# rs422-rs485.net
KiCad netlist of a schematic drawn in Altium Designer
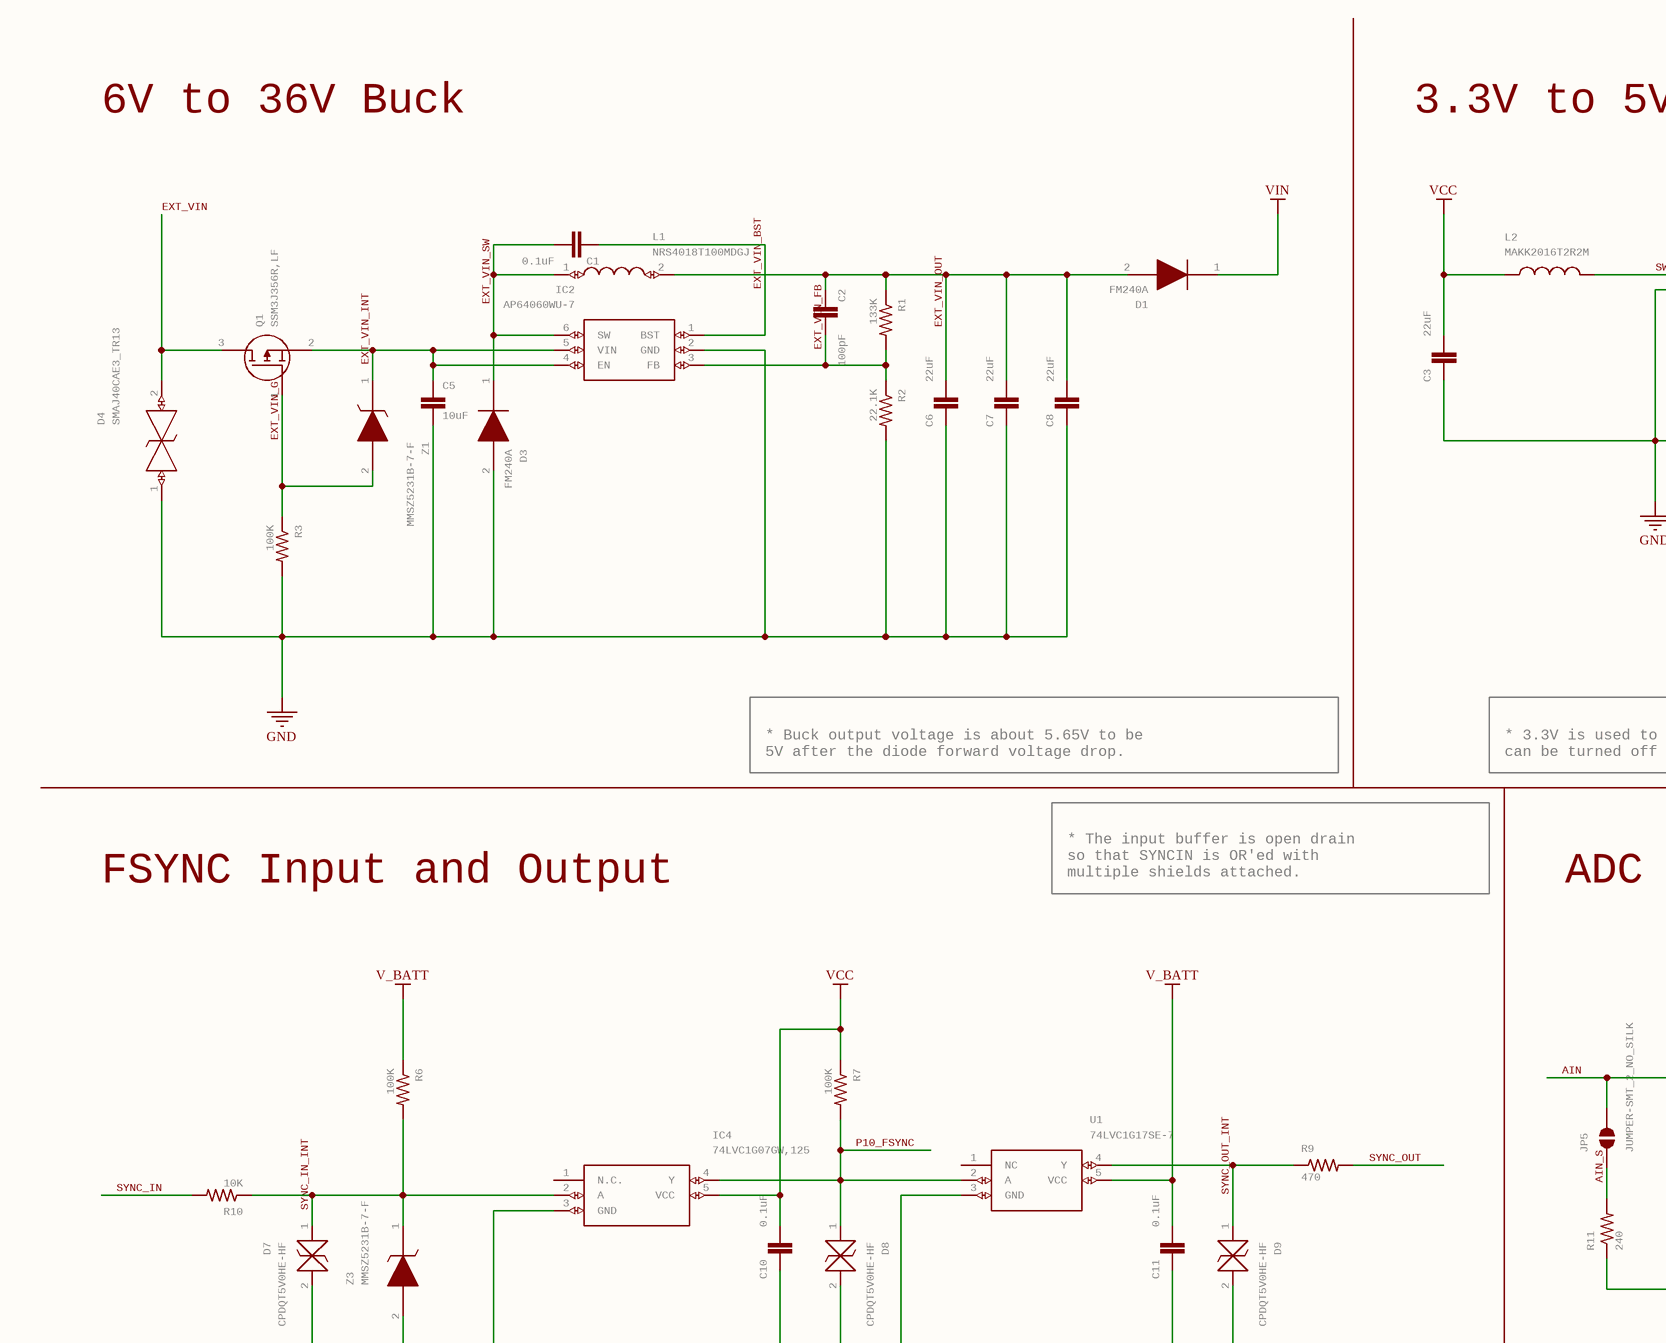
[diagram p0: rs422-rs485.SchDoc, top left]
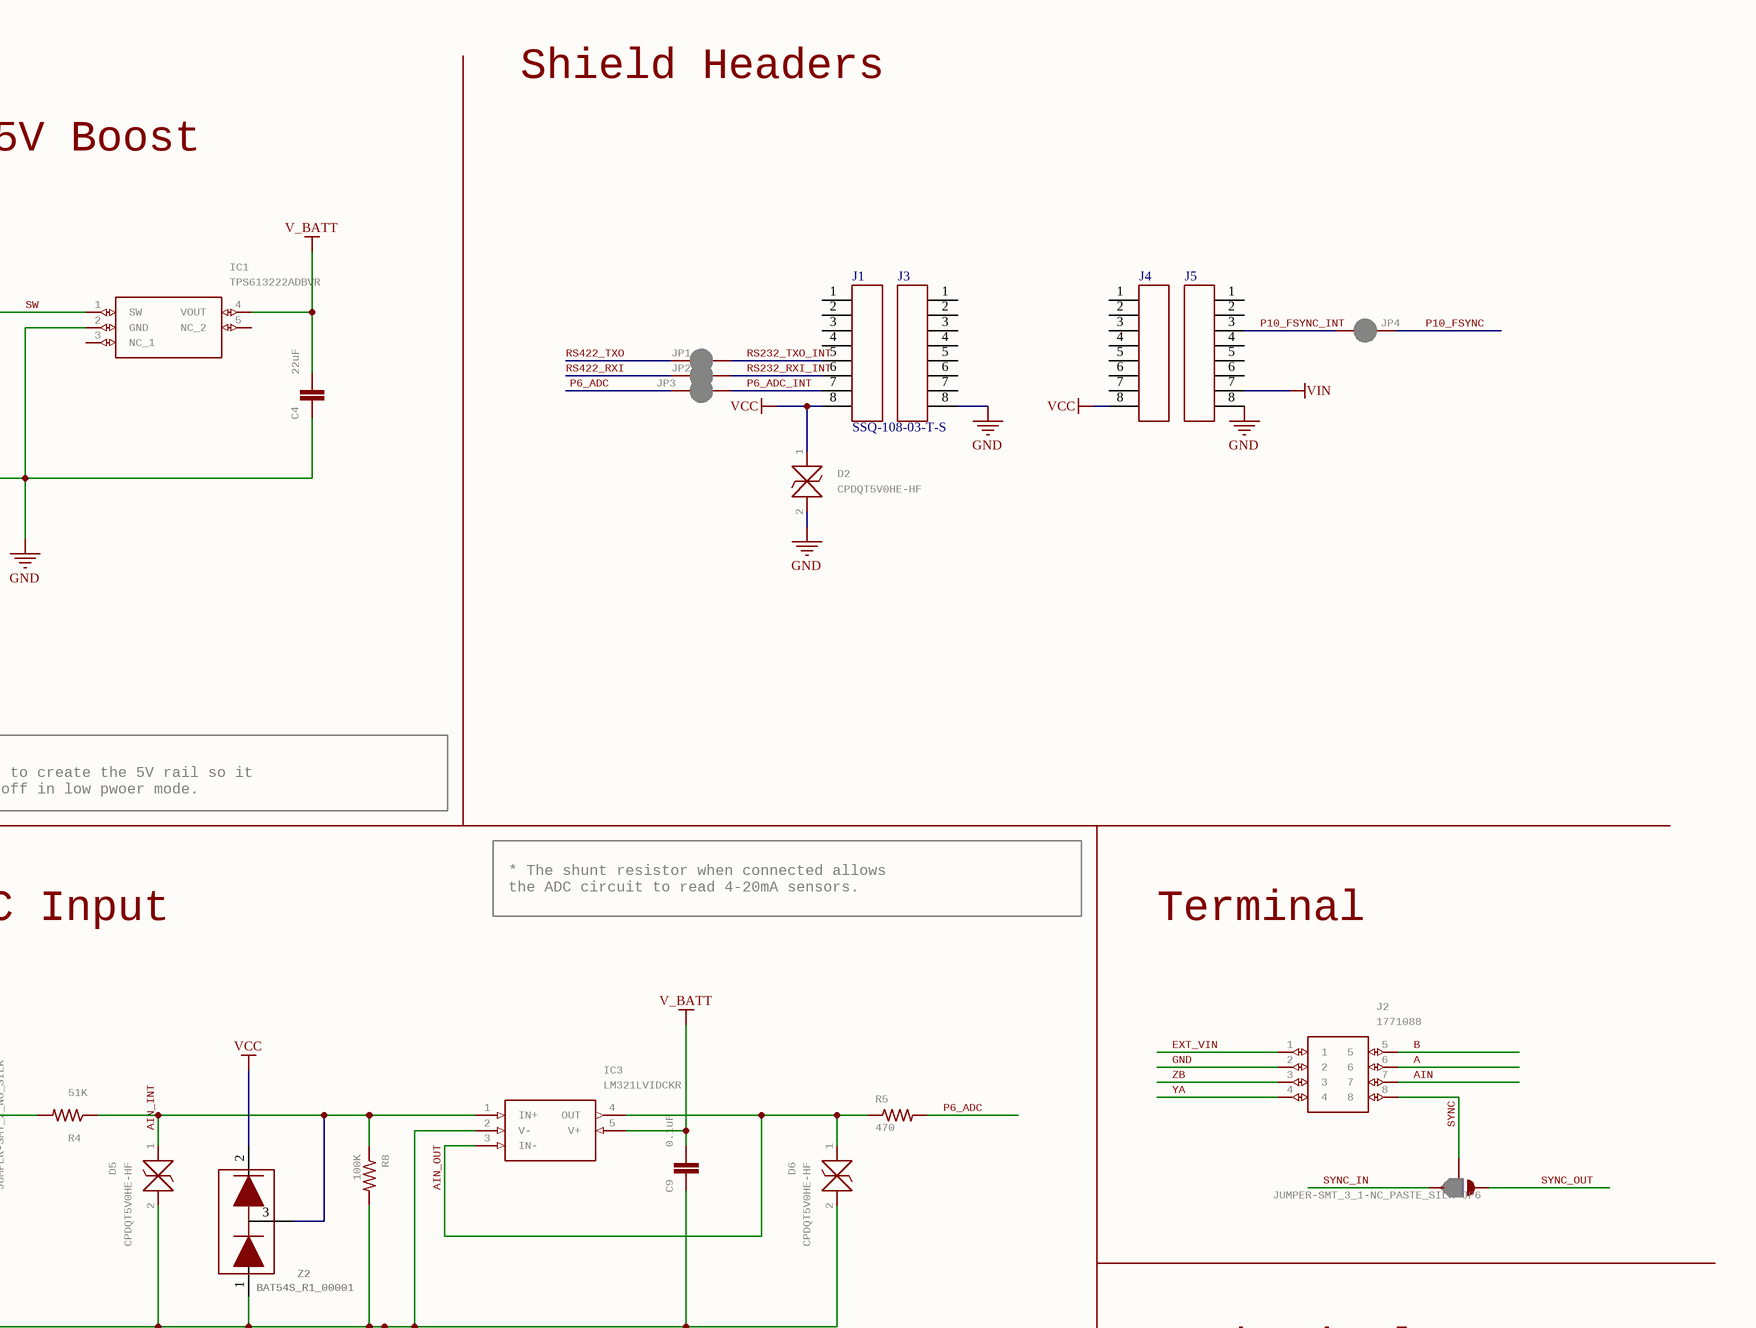
[diagram p1: rs422-rs485.SchDoc, top right]
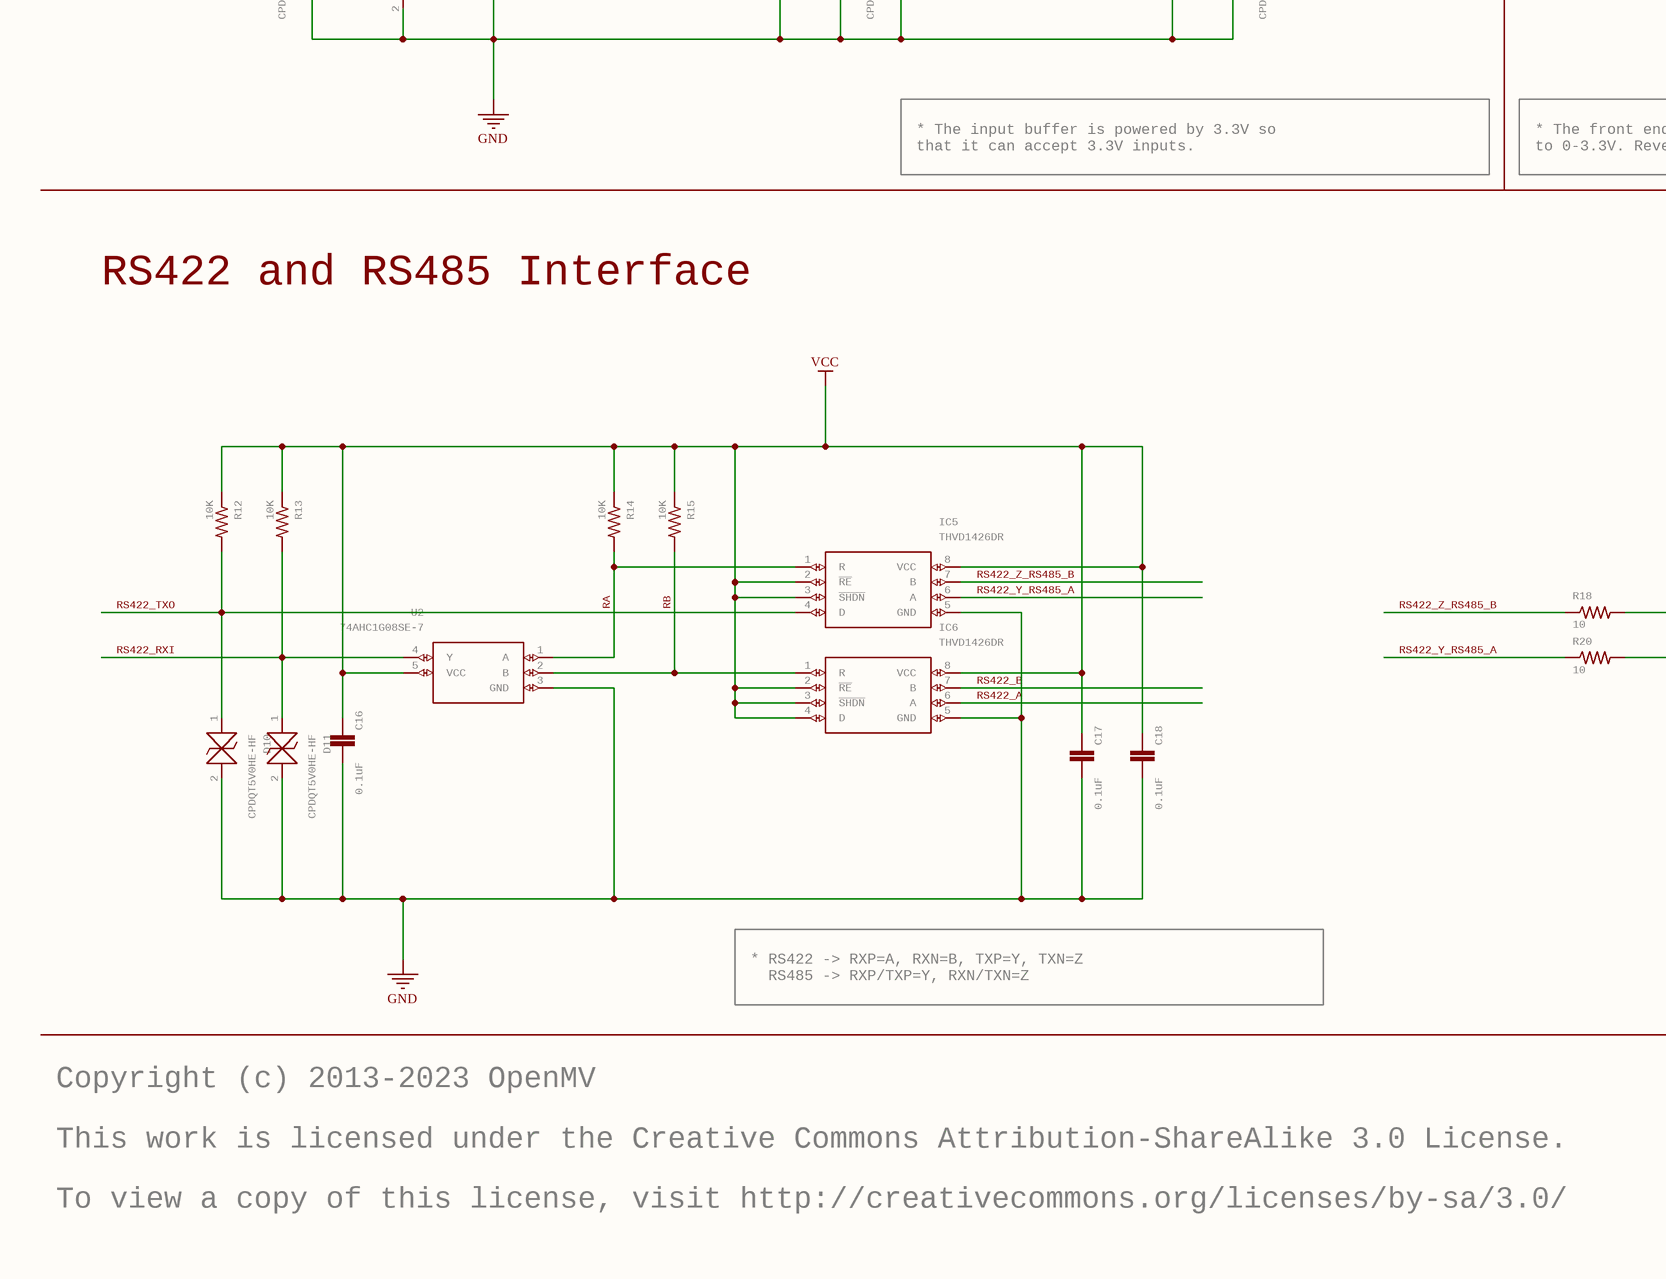
[diagram p2: rs422-rs485.SchDoc, bottom left]
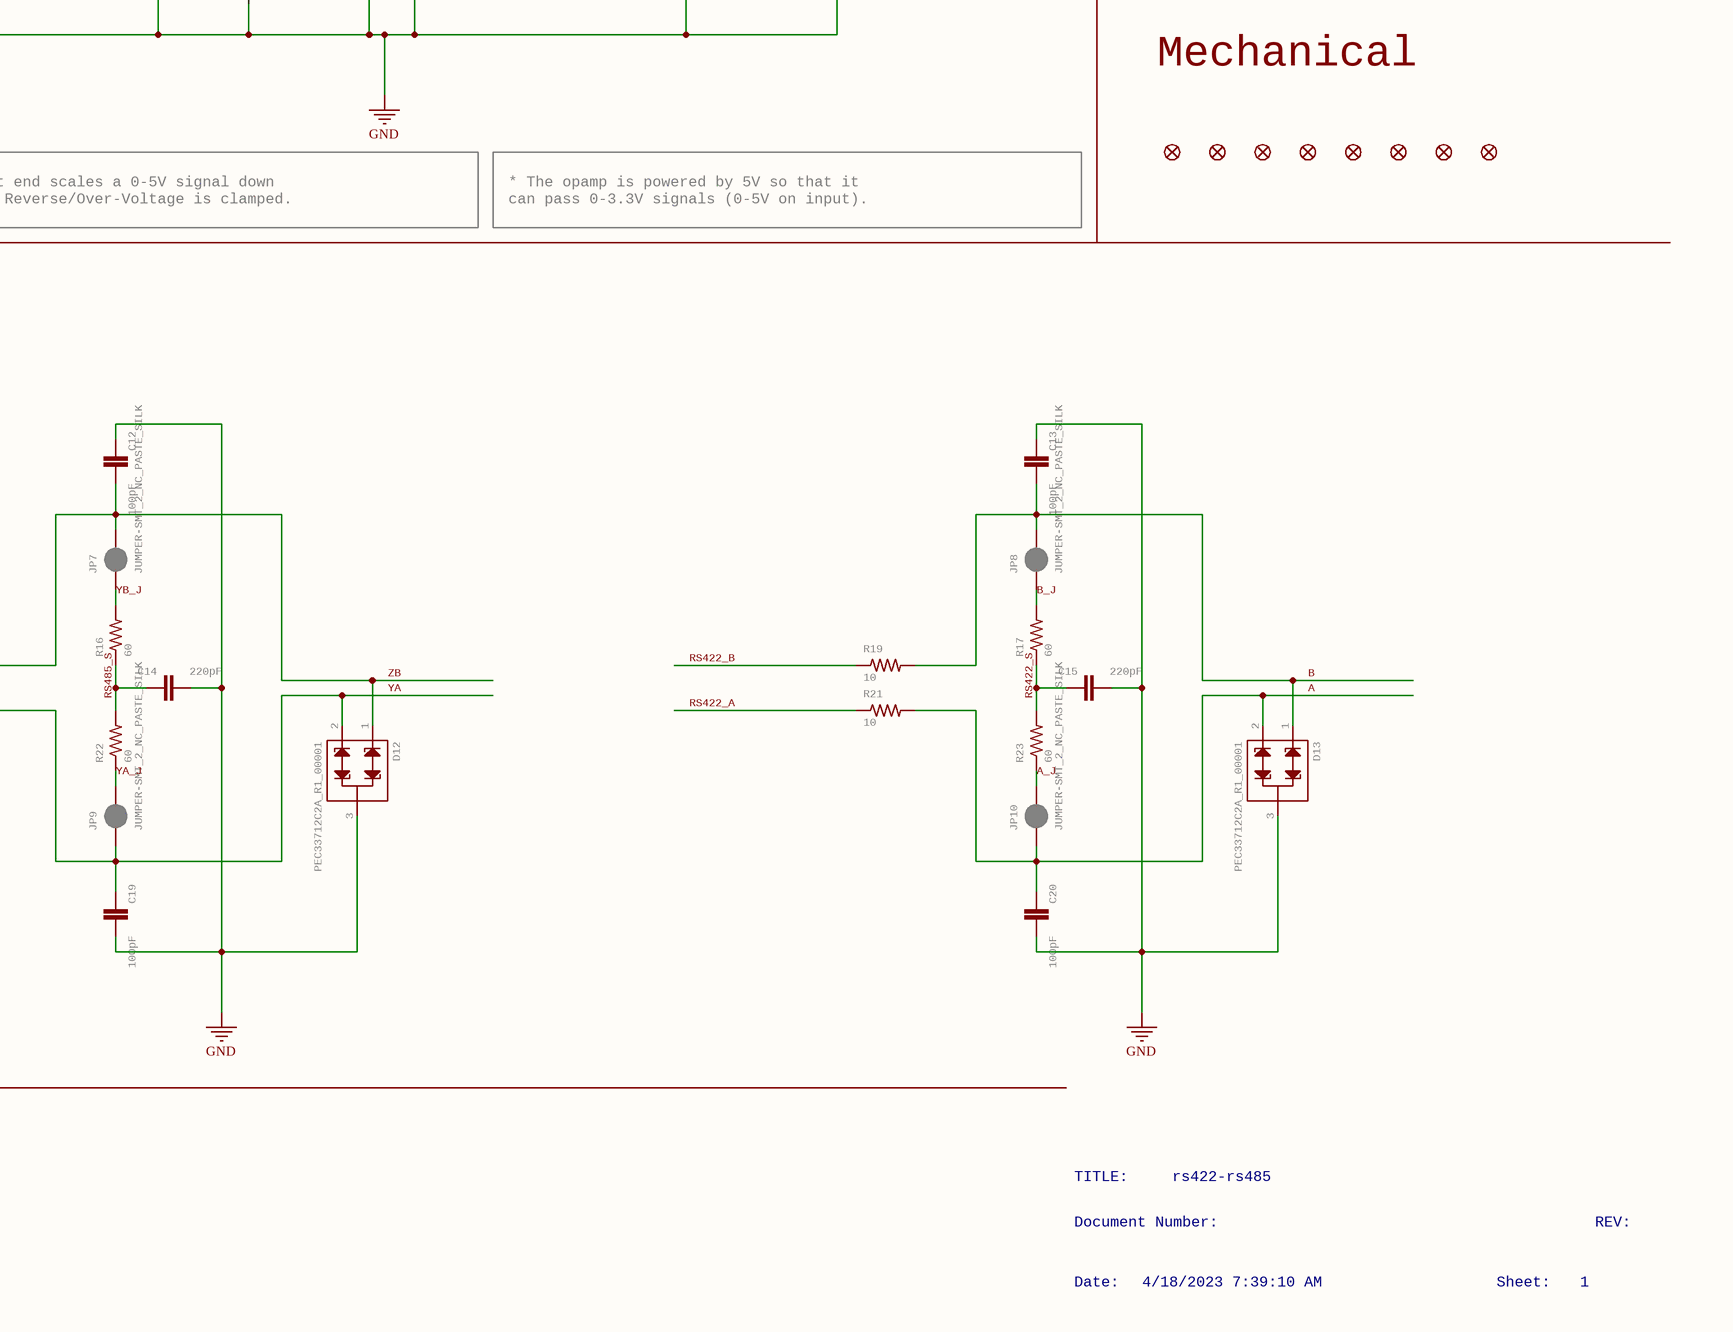
[diagram p3: rs422-rs485.SchDoc, bottom right]

(export (version "E")
  (design (tool "Eeschema 10.0.6"))
  (components
    (comp (ref "C1")
      (value "0.1uF")
      (footprint "0402-CAP")
      (description "CapacitorStandard 0603 ceramic capacitor, and 0.1\" leaded capacitor.")
      (fields (field (name "MPN") "GRM155R71H104KE14D"))
      (libsource (lib "") (part "CAP0402-CAP_3"))
    )
    (comp (ref "C2")
      (value "100pF")
      (footprint "0402-CAP")
      (description "CapacitorStandard 0603 ceramic capacitor, and 0.1\" leaded capacitor.")
      (fields (field (name "MPN") "CC0402JRNPO9BN101"))
      (libsource (lib "rs422-rs485") (part "CAP0402-CAP"))
    )
    (comp (ref "C3")
      (value "22uF")
      (footprint "0805")
      (fields (field (name "MPN") "CL21A226MQQNNNE"))
      (libsource (lib "rs422-rs485") (part "22UF-0805-6.3V-20%"))
    )
    (comp (ref "C4")
      (value "22uF")
      (footprint "0805")
      (fields (field (name "MPN") "CL21A226MQQNNNE"))
      (libsource (lib "rs422-rs485") (part "22UF-0805-6.3V-20%"))
    )
    (comp (ref "C5")
      (value "10uF")
      (footprint "C0805")
      (description "CAPACITOR, European symbol")
      (fields (field (name "MPN") "GRM21BR61H106KE43K"))
      (libsource (lib "rs422-rs485") (part "C-EUC0805"))
    )
    (comp (ref "C6")
      (value "22uF")
      (footprint "0805")
      (fields (field (name "MPN") "CL21A226MQQNNNE"))
      (libsource (lib "rs422-rs485") (part "22UF-0805-6.3V-20%"))
    )
    (comp (ref "C7")
      (value "22uF")
      (footprint "0805")
      (fields (field (name "MPN") "CL21A226MQQNNNE"))
      (libsource (lib "rs422-rs485") (part "22UF-0805-6.3V-20%"))
    )
    (comp (ref "C8")
      (value "22uF")
      (footprint "0805")
      (fields (field (name "MPN") "CL21A226MQQNNNE"))
      (libsource (lib "rs422-rs485") (part "22UF-0805-6.3V-20%"))
    )
    (comp (ref "C9")
      (value "0.1uF")
      (footprint "0402-CAP")
      (description "CapacitorStandard 0603 ceramic capacitor, and 0.1\" leaded capacitor.")
      (fields (field (name "MPN") "GRM155R71H104KE14D"))
      (libsource (lib "") (part "CAP0402-CAP_1"))
    )
    (comp (ref "C10")
      (value "0.1uF")
      (footprint "0402-CAP")
      (description "CapacitorStandard 0603 ceramic capacitor, and 0.1\" leaded capacitor.")
      (fields (field (name "MPN") "GRM155R71H104KE14D"))
      (libsource (lib "") (part "CAP0402-CAP_1"))
    )
    (comp (ref "C11")
      (value "0.1uF")
      (footprint "0402-CAP")
      (description "CapacitorStandard 0603 ceramic capacitor, and 0.1\" leaded capacitor.")
      (fields (field (name "MPN") "GRM155R71H104KE14D"))
      (libsource (lib "") (part "CAP0402-CAP_1"))
    )
    (comp (ref "C12")
      (value "100pF")
      (footprint "0402-CAP")
      (description "CapacitorStandard 0603 ceramic capacitor, and 0.1\" leaded capacitor.")
      (fields (field (name "MPN") "CC0402JRNPO9BN101"))
      (libsource (lib "rs422-rs485") (part "CAP0402-CAP"))
    )
    (comp (ref "C13")
      (value "100pF")
      (footprint "0402-CAP")
      (description "CapacitorStandard 0603 ceramic capacitor, and 0.1\" leaded capacitor.")
      (fields (field (name "MPN") "CC0402JRNPO9BN101"))
      (libsource (lib "rs422-rs485") (part "CAP0402-CAP"))
    )
    (comp (ref "C14")
      (value "220pF")
      (footprint "0402-CAP")
      (description "CapacitorStandard 0603 ceramic capacitor, and 0.1\" leaded capacitor.")
      (fields (field (name "MPN") "0402B221K500CT"))
      (libsource (lib "") (part "CAP0402-CAP_2"))
    )
    (comp (ref "C15")
      (value "220pF")
      (footprint "0402-CAP")
      (description "CapacitorStandard 0603 ceramic capacitor, and 0.1\" leaded capacitor.")
      (fields (field (name "MPN") "0402B221K500CT"))
      (libsource (lib "") (part "CAP0402-CAP_2"))
    )
    (comp (ref "C16")
      (value "0.1uF")
      (footprint "0402-CAP")
      (description "CapacitorStandard 0603 ceramic capacitor, and 0.1\" leaded capacitor.")
      (fields (field (name "MPN") "GRM155R71H104KE14D"))
      (libsource (lib "rs422-rs485") (part "CAP0402-CAP"))
    )
    (comp (ref "C17")
      (value "0.1uF")
      (footprint "0402-CAP")
      (description "CapacitorStandard 0603 ceramic capacitor, and 0.1\" leaded capacitor.")
      (fields (field (name "MPN") "GRM155R71H104KE14D"))
      (libsource (lib "rs422-rs485") (part "CAP0402-CAP"))
    )
    (comp (ref "C18")
      (value "0.1uF")
      (footprint "0402-CAP")
      (description "CapacitorStandard 0603 ceramic capacitor, and 0.1\" leaded capacitor.")
      (fields (field (name "MPN") "GRM155R71H104KE14D"))
      (libsource (lib "rs422-rs485") (part "CAP0402-CAP"))
    )
    (comp (ref "C19")
      (value "100pF")
      (footprint "0402-CAP")
      (description "CapacitorStandard 0603 ceramic capacitor, and 0.1\" leaded capacitor.")
      (fields (field (name "MPN") "CC0402JRNPO9BN101"))
      (libsource (lib "rs422-rs485") (part "CAP0402-CAP"))
    )
    (comp (ref "C20")
      (value "100pF")
      (footprint "0402-CAP")
      (description "CapacitorStandard 0603 ceramic capacitor, and 0.1\" leaded capacitor.")
      (fields (field (name "MPN") "CC0402JRNPO9BN101"))
      (libsource (lib "rs422-rs485") (part "CAP0402-CAP"))
    )
    (comp (ref "D1")
      (value "FM240A")
      (footprint "DIOM5025X231N")
      (description "Diodes - General Purpose, Power, Switching GP Si Rectifier SMB,2A,40V   Source:  Datasheet")
      (fields (field (name "MOUSER_PART_NUMBER") "583-FM240A"))
      (libsource (lib "rs422-rs485") (part "FM240A"))
    )
    (comp (ref "D2")
      (value "CPDQT5V0HE-HF")
      (footprint "CPDQT5V0HEHF")
      (description "ESD Suppressors / TVS Diodes DIODE ESD 5VWM 65W 0402/SOD-923F   Source:  Datasheet")
      (fields (field (name "MOUSER_PART_NUMBER") "MOUSER_PART_NUMBER"))
      (libsource (lib "rs422-rs485") (part "CPDQT5V0HE-HF"))
    )
    (comp (ref "D3")
      (value "FM240A")
      (footprint "DIOM5025X231N")
      (description "Diodes - General Purpose, Power, Switching GP Si Rectifier SMB,2A,40V   Source:  Datasheet")
      (fields (field (name "MOUSER_PART_NUMBER") "583-FM240A"))
      (libsource (lib "rs422-rs485") (part "FM240A"))
    )
    (comp (ref "D4")
      (value "SMAJ40CAE3_TR13")
      (footprint "SMAJ40CAE3TR13")
      (description "ESD Suppressors / TVS Diodes TVS   Source:  Datasheet")
      (fields
        (field (name "MANUFACTURER_PART_NUMBER") "SMAJ40CAe3/TR13")
        (field (name "MOUSER_PART_NUMBER") "494-SMAJ40CAE3/TR13")
      )
      (libsource (lib "rs422-rs485") (part "SMAJ40CAE3_TR13"))
    )
    (comp (ref "D5")
      (value "CPDQT5V0HE-HF")
      (footprint "CPDQT5V0HEHF")
      (description "ESD Suppressors / TVS Diodes DIODE ESD 5VWM 65W 0402/SOD-923F   Source:  Datasheet")
      (fields (field (name "MOUSER_PART_NUMBER") "MOUSER_PART_NUMBER"))
      (libsource (lib "rs422-rs485") (part "CPDQT5V0HE-HF"))
    )
    (comp (ref "D6")
      (value "CPDQT5V0HE-HF")
      (footprint "CPDQT5V0HEHF")
      (description "ESD Suppressors / TVS Diodes DIODE ESD 5VWM 65W 0402/SOD-923F   Source:  Datasheet")
      (fields (field (name "MOUSER_PART_NUMBER") "MOUSER_PART_NUMBER"))
      (libsource (lib "rs422-rs485") (part "CPDQT5V0HE-HF"))
    )
    (comp (ref "D7")
      (value "CPDQT5V0HE-HF")
      (footprint "CPDQT5V0HEHF")
      (description "ESD Suppressors / TVS Diodes DIODE ESD 5VWM 65W 0402/SOD-923F   Source:  Datasheet")
      (fields (field (name "MOUSER_PART_NUMBER") "MOUSER_PART_NUMBER"))
      (libsource (lib "rs422-rs485") (part "CPDQT5V0HE-HF"))
    )
    (comp (ref "D8")
      (value "CPDQT5V0HE-HF")
      (footprint "CPDQT5V0HEHF")
      (description "ESD Suppressors / TVS Diodes DIODE ESD 5VWM 65W 0402/SOD-923F   Source:  Datasheet")
      (fields (field (name "MOUSER_PART_NUMBER") "MOUSER_PART_NUMBER"))
      (libsource (lib "rs422-rs485") (part "CPDQT5V0HE-HF"))
    )
    (comp (ref "D9")
      (value "CPDQT5V0HE-HF")
      (footprint "CPDQT5V0HEHF")
      (description "ESD Suppressors / TVS Diodes DIODE ESD 5VWM 65W 0402/SOD-923F   Source:  Datasheet")
      (fields (field (name "MOUSER_PART_NUMBER") "MOUSER_PART_NUMBER"))
      (libsource (lib "rs422-rs485") (part "CPDQT5V0HE-HF"))
    )
    (comp (ref "D10")
      (value "CPDQT5V0HE-HF")
      (footprint "CPDQT5V0HEHF")
      (description "ESD Suppressors / TVS Diodes DIODE ESD 5VWM 65W 0402/SOD-923F   Source:  Datasheet")
      (fields (field (name "MOUSER_PART_NUMBER") "MOUSER_PART_NUMBER"))
      (libsource (lib "rs422-rs485") (part "CPDQT5V0HE-HF"))
    )
    (comp (ref "D11")
      (value "CPDQT5V0HE-HF")
      (footprint "CPDQT5V0HEHF")
      (description "ESD Suppressors / TVS Diodes DIODE ESD 5VWM 65W 0402/SOD-923F   Source:  Datasheet")
      (fields (field (name "MOUSER_PART_NUMBER") "MOUSER_PART_NUMBER"))
      (libsource (lib "rs422-rs485") (part "CPDQT5V0HE-HF"))
    )
    (comp (ref "D12")
      (value "PEC33712C2A_R1_00001")
      (footprint "SOT23-3")
      (libsource (lib "rs422-rs485") (part "PESD1CAN"))
    )
    (comp (ref "D13")
      (value "PEC33712C2A_R1_00001")
      (footprint "SOT23-3")
      (libsource (lib "rs422-rs485") (part "PESD1CAN"))
    )
    (comp (ref "FD1")
      (value "FIDUCIAL1X2")
      (footprint "FIDUCIAL-1X2")
      (fields (field (name "LIBRARYNAME") "SparkFun-Aesthetics"))
      (libsource (lib "rs422-rs485") (part "FIDUCIAL1X2"))
    )
    (comp (ref "FD2")
      (value "FIDUCIAL1X2")
      (footprint "FIDUCIAL-1X2")
      (fields (field (name "LIBRARYNAME") "SparkFun-Aesthetics"))
      (libsource (lib "rs422-rs485") (part "FIDUCIAL1X2"))
    )
    (comp (ref "FD3")
      (value "FIDUCIAL1X2")
      (footprint "FIDUCIAL-1X2")
      (fields (field (name "LIBRARYNAME") "SparkFun-Aesthetics"))
      (libsource (lib "rs422-rs485") (part "FIDUCIAL1X2"))
    )
    (comp (ref "FD4")
      (value "FIDUCIAL1X2")
      (footprint "FIDUCIAL-1X2")
      (fields (field (name "LIBRARYNAME") "SparkFun-Aesthetics"))
      (libsource (lib "rs422-rs485") (part "FIDUCIAL1X2"))
    )
    (comp (ref "FD5")
      (value "FIDUCIAL1X2")
      (footprint "FIDUCIAL-1X2")
      (fields (field (name "LIBRARYNAME") "SparkFun-Aesthetics"))
      (libsource (lib "rs422-rs485") (part "FIDUCIAL1X2"))
    )
    (comp (ref "FD6")
      (value "FIDUCIAL1X2")
      (footprint "FIDUCIAL-1X2")
      (fields (field (name "LIBRARYNAME") "SparkFun-Aesthetics"))
      (libsource (lib "rs422-rs485") (part "FIDUCIAL1X2"))
    )
    (comp (ref "FD7")
      (value "FIDUCIAL1X2")
      (footprint "FIDUCIAL-1X2")
      (fields (field (name "LIBRARYNAME") "SparkFun-Aesthetics"))
      (libsource (lib "rs422-rs485") (part "FIDUCIAL1X2"))
    )
    (comp (ref "FD8")
      (value "FIDUCIAL1X2")
      (footprint "FIDUCIAL-1X2")
      (fields (field (name "LIBRARYNAME") "SparkFun-Aesthetics"))
      (libsource (lib "rs422-rs485") (part "FIDUCIAL1X2"))
    )
    (comp (ref "IC1")
      (value "TPS613222ADBVR")
      (footprint "SOT95P280X145-5N")
      (description "6-uA Quiescent Current, 1.8-A Switch Current Boost Converter   Source:  Datasheet")
      (fields (field (name "MOUSER_PART_NUMBER") "595-TPS613222ADBVR"))
      (libsource (lib "rs422-rs485") (part "TPS613222ADBVR"))
    )
    (comp (ref "IC2")
      (value "AP64060WU-7")
      (footprint "SOT95P280X100-6N")
      (description "Switching Voltage Regulators DCDC Conv HV Buck TSOT26(STD) T&R 3K   Source:  Datasheet")
      (fields (field (name "MOUSER_PART_NUMBER") "621-AP64060WU-7"))
      (libsource (lib "rs422-rs485") (part "AP64060WU-7"))
    )
    (comp (ref "IC3")
      (value "LM321LVIDCKR")
      (footprint "SOT65P210X110-5N")
      (description "1-Channel industry standard low voltage operational amplifier   Source:  Datasheet")
      (fields (field (name "MOUSER_PART_NUMBER") "595-LM321LVIDCKR"))
      (libsource (lib "rs422-rs485") (part "LM321LVIDCKR"))
    )
    (comp (ref "IC4")
      (value "74LVC1G07GW,125")
      (footprint "SOT65P212X110-5N")
      (description "74LVC1G07 - Buffer with open-drain output@en-us   Source:  Datasheet")
      (fields (field (name "MOUSER_PART_NUMBER") "771-74LVC1G07GW-G"))
      (libsource (lib "rs422-rs485") (part "74LVC1G07GW,125"))
    )
    (comp (ref "IC5")
      (value "THVD1426DR")
      (footprint "SOIC127P600X175-8N")
      (fields (field (name "MOUSER_PART_NUMBER") "595-THVD1426DR"))
      (libsource (lib "rs422-rs485") (part "THVD1426DR"))
    )
    (comp (ref "IC6")
      (value "THVD1426DR")
      (footprint "SOIC127P600X175-8N")
      (fields (field (name "MOUSER_PART_NUMBER") "595-THVD1426DR"))
      (libsource (lib "rs422-rs485") (part "THVD1426DR"))
    )
    (comp (ref "J1") (value "SSQ-108-03-T-S") (footprint "HDR_1X8") (libsource (lib "pir") (part "HDR_1X8")))
    (comp (ref "J2")
      (value "1771088")
      (footprint "1771088")
      (fields (field (name "MOUSER_PART_NUMBER") "651-1771088"))
      (libsource (lib "rs422-rs485") (part "1771088"))
    )
    (comp (ref "J3") (value "SSQ-108-03-T-S") (footprint "HDR_1X8") (libsource (lib "") (part "HDR_1X8_1")))
    (comp (ref "J4") (value "SSQ-108-03-T-S") (footprint "HDR_1X8") (libsource (lib "pir") (part "HDR_1X8")))
    (comp (ref "J5") (value "SSQ-108-03-T-S") (footprint "HDR_1X8") (libsource (lib "") (part "HDR_1X8_1")))
    (comp (ref "JP1")
      (value "JUMPER-SMT_2_NC_PASTE_SILK")
      (footprint "SMT-JUMPER_2_NC_PASTE_SILK")
      (libsource (lib "rs422-rs485") (part "JUMPER-SMT_2_NC_PASTE_SILK"))
    )
    (comp (ref "JP2")
      (value "JUMPER-SMT_2_NC_PASTE_SILK")
      (footprint "SMT-JUMPER_2_NC_PASTE_SILK")
      (libsource (lib "rs422-rs485") (part "JUMPER-SMT_2_NC_PASTE_SILK"))
    )
    (comp (ref "JP3")
      (value "JUMPER-SMT_2_NC_PASTE_SILK")
      (footprint "SMT-JUMPER_2_NC_PASTE_SILK")
      (libsource (lib "rs422-rs485") (part "JUMPER-SMT_2_NC_PASTE_SILK"))
    )
    (comp (ref "JP4")
      (value "JUMPER-SMT_2_NC_PASTE_SILK")
      (footprint "SMT-JUMPER_2_NC_PASTE_SILK")
      (libsource (lib "rs422-rs485") (part "JUMPER-SMT_2_NC_PASTE_SILK"))
    )
    (comp (ref "JP5")
      (value "JUMPER-SMT_2_NO_SILK")
      (footprint "SMT-JUMPER_2_NO_SILK")
      (libsource (lib "rs422-rs485") (part "JUMPER-SMT_2_NO_SILK"))
    )
    (comp (ref "JP6")
      (value "JUMPER-SMT_3_1-NC_PASTE_SILK")
      (footprint "SMT-JUMPER_3_1-NC_PASTE_SILK")
      (libsource (lib "rs422-rs485") (part "JUMPER-SMT_3_1-NC_PASTE_SILK"))
    )
    (comp (ref "JP7")
      (value "JUMPER-SMT_2_NC_PASTE_SILK")
      (footprint "SMT-JUMPER_2_NC_PASTE_SILK")
      (libsource (lib "rs422-rs485") (part "JUMPER-SMT_2_NC_PASTE_SILK"))
    )
    (comp (ref "JP8")
      (value "JUMPER-SMT_2_NC_PASTE_SILK")
      (footprint "SMT-JUMPER_2_NC_PASTE_SILK")
      (libsource (lib "rs422-rs485") (part "JUMPER-SMT_2_NC_PASTE_SILK"))
    )
    (comp (ref "JP9")
      (value "JUMPER-SMT_2_NC_PASTE_SILK")
      (footprint "SMT-JUMPER_2_NC_PASTE_SILK")
      (libsource (lib "rs422-rs485") (part "JUMPER-SMT_2_NC_PASTE_SILK"))
    )
    (comp (ref "JP10")
      (value "JUMPER-SMT_2_NC_PASTE_SILK")
      (footprint "SMT-JUMPER_2_NC_PASTE_SILK")
      (libsource (lib "rs422-rs485") (part "JUMPER-SMT_2_NC_PASTE_SILK"))
    )
    (comp (ref "L1")
      (value "NRS4018T100MDGJ")
      (footprint "NRS4018T100MDGJ")
      (description "Fixed Inductors 4018 10uH 180mOhms +/-20%Tol 1200mA   Source:  Datasheet")
      (fields (field (name "MOUSER_PART_NUMBER") "963-NRS4018T100MDGJ"))
      (libsource (lib "rs422-rs485") (part "NRS4018T100MDGJ"))
    )
    (comp (ref "L2")
      (value "MAKK2016T2R2M")
      (footprint "INDC2016X100N")
      (description "INDUCTOR, METAL CORE Check availability")
      (fields (field (name "MF") "Taiyo Yuden"))
      (libsource (lib "rs422-rs485") (part "MAKK2016T2R2M"))
    )
    (comp (ref "Q1")
      (value "SSM3J356R,LF")
      (footprint "SOTFL95P240X88-3N")
      (description "MOSFET Small-signal MOSFET ID: -2A, VDSS: -60V   Source:  Datasheet")
      (fields (field (name "MOUSER_PART_NUMBER") "757-SSM3J356RLF"))
      (libsource (lib "rs422-rs485") (part "SSM3J356R,LF"))
    )
    (comp (ref "R1")
      (value "133K")
      (footprint "0402-RES")
      (description "ResistorBasic schematic elements and footprints for 0603, 1206, and PTH resistors.")
      (fields (field (name "MPN") "RC0402FR-07133KL"))
      (libsource (lib "rs422-rs485") (part "RESISTOR0402-RES"))
    )
    (comp (ref "R2")
      (value "22.1K")
      (footprint "0402-RES")
      (description "ResistorBasic schematic elements and footprints for 0603, 1206, and PTH resistors.")
      (fields (field (name "MPN") "CR0402-FX-2212GLF"))
      (libsource (lib "rs422-rs485") (part "RESISTOR0402-RES"))
    )
    (comp (ref "R3")
      (value "100K")
      (footprint "0402-RES")
      (description "ResistorBasic schematic elements and footprints for 0603, 1206, and PTH resistors.")
      (fields (field (name "MPN") "AC0402FR-07100KL"))
      (libsource (lib "rs422-rs485") (part "RESISTOR0402-RES"))
    )
    (comp (ref "R4")
      (value "51K")
      (footprint "0402-RES")
      (description "ResistorBasic schematic elements and footprints for 0603, 1206, and PTH resistors.")
      (fields (field (name "MPN") "RC0402JR-0751KL"))
      (libsource (lib "rs422-rs485") (part "RESISTOR0402-RES"))
    )
    (comp (ref "R5")
      (value "470")
      (footprint "R0603")
      (description "RESISTOR, American symbol")
      (fields (field (name "MPN") "CR0603-FX-4700ELF"))
      (libsource (lib "rs422-rs485") (part "R-US_R0603"))
    )
    (comp (ref "R6")
      (value "100K")
      (footprint "0402-RES")
      (description "ResistorBasic schematic elements and footprints for 0603, 1206, and PTH resistors.")
      (fields (field (name "MPN") "AC0402FR-07100KL"))
      (libsource (lib "rs422-rs485") (part "RESISTOR0402-RES"))
    )
    (comp (ref "R7")
      (value "100K")
      (footprint "0402-RES")
      (description "ResistorBasic schematic elements and footprints for 0603, 1206, and PTH resistors.")
      (fields (field (name "MPN") "AC0402FR-07100KL"))
      (libsource (lib "rs422-rs485") (part "RESISTOR0402-RES"))
    )
    (comp (ref "R8")
      (value "100K")
      (footprint "0402-RES")
      (description "ResistorBasic schematic elements and footprints for 0603, 1206, and PTH resistors.")
      (fields (field (name "MPN") "AC0402FR-07100KL"))
      (libsource (lib "rs422-rs485") (part "RESISTOR0402-RES"))
    )
    (comp (ref "R9")
      (value "470")
      (footprint "R0603")
      (description "RESISTOR, American symbol")
      (fields (field (name "MPN") "CR0603-FX-4700ELF"))
      (libsource (lib "rs422-rs485") (part "R-US_R0603"))
    )
    (comp (ref "R10")
      (value "10K")
      (footprint "0402-RES")
      (description "ResistorBasic schematic elements and footprints for 0603, 1206, and PTH resistors.")
      (fields (field (name "MPN") "AC0402FR-1310KL"))
      (libsource (lib "rs422-rs485") (part "RESISTOR0402-RES"))
    )
    (comp (ref "R11")
      (value "240")
      (footprint "R0603")
      (description "RESISTOR, American symbol")
      (fields (field (name "MPN") "RK73B1JTTD241J"))
      (libsource (lib "rs422-rs485") (part "R-US_R0603"))
    )
    (comp (ref "R12")
      (value "10K")
      (footprint "0402-RES")
      (description "ResistorBasic schematic elements and footprints for 0603, 1206, and PTH resistors.")
      (fields (field (name "MPN") "AC0402FR-1310KL"))
      (libsource (lib "rs422-rs485") (part "RESISTOR0402-RES"))
    )
    (comp (ref "R13")
      (value "10K")
      (footprint "0402-RES")
      (description "ResistorBasic schematic elements and footprints for 0603, 1206, and PTH resistors.")
      (fields (field (name "MPN") "AC0402FR-1310KL"))
      (libsource (lib "rs422-rs485") (part "RESISTOR0402-RES"))
    )
    (comp (ref "R14")
      (value "10K")
      (footprint "0402-RES")
      (description "ResistorBasic schematic elements and footprints for 0603, 1206, and PTH resistors.")
      (fields (field (name "MPN") "AC0402FR-1310KL"))
      (libsource (lib "rs422-rs485") (part "RESISTOR0402-RES"))
    )
    (comp (ref "R15")
      (value "10K")
      (footprint "0402-RES")
      (description "ResistorBasic schematic elements and footprints for 0603, 1206, and PTH resistors.")
      (fields (field (name "MPN") "AC0402FR-1310KL"))
      (libsource (lib "rs422-rs485") (part "RESISTOR0402-RES"))
    )
    (comp (ref "R16")
      (value "60")
      (footprint "R1206")
      (description "RESISTOR, American symbol")
      (fields (field (name "MPN") "RC1206FR-0760R4L"))
      (libsource (lib "rs422-rs485") (part "R-US_R1206"))
    )
    (comp (ref "R17")
      (value "60")
      (footprint "R1206")
      (description "RESISTOR, American symbol")
      (fields (field (name "MPN") "RC1206FR-0760R4L"))
      (libsource (lib "rs422-rs485") (part "R-US_R1206"))
    )
    (comp (ref "R18")
      (value "10")
      (footprint "R0805")
      (description "RESISTOR, American symbol")
      (fields (field (name "MPN") "RK73B2ATTD100J"))
      (libsource (lib "rs422-rs485") (part "R-US_R0805"))
    )
    (comp (ref "R19")
      (value "10")
      (footprint "R0805")
      (description "RESISTOR, American symbol")
      (fields (field (name "MPN") "RK73B2ATTD100J"))
      (libsource (lib "rs422-rs485") (part "R-US_R0805"))
    )
    (comp (ref "R20")
      (value "10")
      (footprint "R0805")
      (description "RESISTOR, American symbol")
      (fields (field (name "MPN") "RK73B2ATTD100J"))
      (libsource (lib "rs422-rs485") (part "R-US_R0805"))
    )
    (comp (ref "R21")
      (value "10")
      (footprint "R0805")
      (description "RESISTOR, American symbol")
      (fields (field (name "MPN") "RK73B2ATTD100J"))
      (libsource (lib "rs422-rs485") (part "R-US_R0805"))
    )
    (comp (ref "R22")
      (value "60")
      (footprint "R1206")
      (description "RESISTOR, American symbol")
      (fields (field (name "MPN") "RC1206FR-0760R4L"))
      (libsource (lib "rs422-rs485") (part "R-US_R1206"))
    )
    (comp (ref "R23")
      (value "60")
      (footprint "R1206")
      (description "RESISTOR, American symbol")
      (fields (field (name "MPN") "RC1206FR-0760R4L"))
      (libsource (lib "rs422-rs485") (part "R-US_R1206"))
    )
    (comp (ref "U1")
      (value "74LVC1G17SE-7")
      (footprint "SOT65P210X110-5N")
      (fields (field (name "MOUSER_PART_NUMBER") "621-74LVC1G17SE-7"))
      (libsource (lib "rs422-rs485") (part "74LVC1G17SE-7"))
    )
    (comp (ref "U2")
      (value "74AHC1G08SE-7")
      (footprint "SOT65P210X110-5N")
      (fields (field (name "MOUSER_PART_NUMBER") "621-74AHC1G08SE-7"))
      (libsource (lib "rs422-rs485") (part "74AHC1G08SE-7"))
    )
    (comp (ref "Z1")
      (value "MMSZ5231B-7-F")
      (footprint "SOD3716X145N")
      (fields (field (name "MOUSER_PART_NUMBER") "621-MMSZ5231B-F"))
      (libsource (lib "rs422-rs485") (part "MMSZ5231B-7-F"))
    )
    (comp (ref "Z2")
      (value "BAT54S_R1_00001")
      (footprint "SOT23-3")
      (libsource (lib "can-rs232") (part "BAT54S_R1_00001"))
    )
    (comp (ref "Z3")
      (value "MMSZ5231B-7-F")
      (footprint "SOD3716X145N")
      (fields (field (name "MOUSER_PART_NUMBER") "621-MMSZ5231B-F"))
      (libsource (lib "rs422-rs485") (part "MMSZ5231B-7-F"))
    )
  )
  (nets
    (net (code "1") (name "/A") (class "Default")
      (node (ref "C20") (pin "1") (pinfunction "1_1") (pintype "passive"))
      (node (ref "D13") (pin "2") (pinfunction "2_2") (pintype "bidirectional"))
      (node (ref "J2") (pin "6") (pinfunction "6_6") (pintype "bidirectional"))
      (node (ref "JP10") (pin "1") (pinfunction "1_1") (pintype "passive"))
      (node (ref "R21") (pin "2") (pinfunction "2_2") (pintype "passive"))
    )
    (net (code "2") (name "/AIN") (class "Default")
      (node (ref "J2") (pin "7") (pinfunction "7_7") (pintype "bidirectional"))
      (node (ref "JP5") (pin "2") (pinfunction "2_2") (pintype "passive"))
      (node (ref "R4") (pin "2") (pinfunction "2_2") (pintype "passive"))
    )
    (net (code "3") (name "/AIN_INT") (class "Default")
      (node (ref "D5") (pin "1") (pinfunction "1_1") (pintype "bidirectional"))
      (node (ref "IC3") (pin "1") (pinfunction "IN+_1") (pintype "input"))
      (node (ref "R4") (pin "1") (pinfunction "1_1") (pintype "passive"))
      (node (ref "R8") (pin "1") (pinfunction "1_1") (pintype "passive"))
      (node (ref "Z2") (pin "3") (pintype "passive"))
    )
    (net (code "4") (name "/AIN_OUT") (class "Default")
      (node (ref "D6") (pin "1") (pinfunction "1_1") (pintype "bidirectional"))
      (node (ref "IC3") (pin "3") (pinfunction "IN-_3") (pintype "input"))
      (node (ref "IC3") (pin "4") (pinfunction "OUT_4") (pintype "output"))
      (node (ref "R5") (pin "1") (pinfunction "1_1") (pintype "passive"))
    )
    (net (code "5") (name "/AIN_S") (class "Default")
      (node (ref "JP5") (pin "1") (pinfunction "1_1") (pintype "passive"))
      (node (ref "R11") (pin "2") (pinfunction "2_2") (pintype "passive"))
    )
    (net (code "6") (name "/A_J") (class "Default")
      (node (ref "JP10") (pin "2") (pinfunction "2_2") (pintype "passive"))
      (node (ref "R23") (pin "1") (pinfunction "1_1") (pintype "passive"))
    )
    (net (code "7") (name "/B") (class "Default")
      (node (ref "C13") (pin "2") (pinfunction "2_2") (pintype "passive"))
      (node (ref "D13") (pin "1") (pinfunction "1_1") (pintype "bidirectional"))
      (node (ref "J2") (pin "5") (pinfunction "5_5") (pintype "bidirectional"))
      (node (ref "JP8") (pin "2") (pinfunction "2_2") (pintype "passive"))
      (node (ref "R19") (pin "2") (pinfunction "2_2") (pintype "passive"))
    )
    (net (code "8") (name "/B_J") (class "Default")
      (node (ref "JP8") (pin "1") (pinfunction "1_1") (pintype "passive"))
      (node (ref "R17") (pin "2") (pinfunction "2_2") (pintype "passive"))
    )
    (net (code "9") (name "/EXT_VIN") (class "Default")
      (node (ref "D4") (pin "2") (pinfunction "2_2") (pintype "bidirectional"))
      (node (ref "J2") (pin "1") (pinfunction "1_1") (pintype "bidirectional"))
      (node (ref "Q1") (pin "3") (pinfunction "D_3") (pintype "bidirectional"))
    )
    (net (code "10") (name "/EXT_VIN_BST") (class "Default")
      (node (ref "C1") (pin "1") (pinfunction "1_1") (pintype "passive"))
      (node (ref "IC2") (pin "1") (pinfunction "BST_1") (pintype "bidirectional"))
    )
    (net (code "11") (name "/EXT_VIN_FB") (class "Default")
      (node (ref "C2") (pin "2") (pinfunction "2_2") (pintype "passive"))
      (node (ref "IC2") (pin "3") (pinfunction "FB_3") (pintype "bidirectional"))
      (node (ref "R1") (pin "2") (pinfunction "2_2") (pintype "passive"))
      (node (ref "R2") (pin "1") (pinfunction "1_1") (pintype "passive"))
    )
    (net (code "12") (name "/EXT_VIN_G") (class "Default")
      (node (ref "Q1") (pin "1") (pinfunction "G_1") (pintype "bidirectional"))
      (node (ref "R3") (pin "1") (pinfunction "1_1") (pintype "passive"))
      (node (ref "Z1") (pin "2") (pinfunction "A_2") (pintype "bidirectional"))
    )
    (net (code "13") (name "/EXT_VIN_INT") (class "Default")
      (node (ref "C5") (pin "1") (pinfunction "1_1") (pintype "passive"))
      (node (ref "IC2") (pin "4") (pinfunction "EN_4") (pintype "bidirectional"))
      (node (ref "IC2") (pin "5") (pinfunction "VIN_5") (pintype "bidirectional"))
      (node (ref "Q1") (pin "2") (pinfunction "S_2") (pintype "bidirectional"))
      (node (ref "Z1") (pin "1") (pinfunction "K_1") (pintype "bidirectional"))
    )
    (net (code "14") (name "/EXT_VIN_OUT") (class "Default")
      (node (ref "C2") (pin "1") (pinfunction "1_1") (pintype "passive"))
      (node (ref "C6") (pin "2") (pinfunction "2_2") (pintype "passive"))
      (node (ref "C7") (pin "2") (pinfunction "2_2") (pintype "passive"))
      (node (ref "C8") (pin "2") (pinfunction "2_2") (pintype "passive"))
      (node (ref "D1") (pin "2") (pinfunction "A_2") (pintype "bidirectional"))
      (node (ref "L1") (pin "2") (pinfunction "2_2") (pintype "bidirectional"))
      (node (ref "R1") (pin "1") (pinfunction "1_1") (pintype "passive"))
    )
    (net (code "15") (name "/EXT_VIN_SW") (class "Default")
      (node (ref "C1") (pin "2") (pinfunction "2_2") (pintype "passive"))
      (node (ref "D3") (pin "1") (pinfunction "K_1") (pintype "bidirectional"))
      (node (ref "IC2") (pin "6") (pinfunction "SW_6") (pintype "bidirectional"))
      (node (ref "L1") (pin "1") (pinfunction "1_1") (pintype "bidirectional"))
    )
    (net (code "16") (name "/P6_ADC") (class "Default")
      (node (ref "JP3") (pin "2") (pinfunction "2_2") (pintype "passive"))
      (node (ref "R5") (pin "2") (pinfunction "2_2") (pintype "passive"))
    )
    (net (code "17") (name "/P6_ADC_INT") (class "Default")
      (node (ref "J1") (pin "7") (pintype "passive"))
      (node (ref "JP3") (pin "1") (pinfunction "1_1") (pintype "passive"))
    )
    (net (code "18") (name "/P10_FSYNC") (class "Default")
      (node (ref "D8") (pin "1") (pinfunction "1_1") (pintype "bidirectional"))
      (node (ref "IC4") (pin "4") (pinfunction "Y_4") (pintype "bidirectional"))
      (node (ref "JP4") (pin "2") (pinfunction "2_2") (pintype "passive"))
      (node (ref "R7") (pin "2") (pinfunction "2_2") (pintype "passive"))
      (node (ref "U1") (pin "2") (pinfunction "A_2") (pintype "bidirectional"))
    )
    (net (code "19") (name "/P10_FSYNC_INT") (class "Default")
      (node (ref "J5") (pin "3") (pintype "passive"))
      (node (ref "JP4") (pin "1") (pinfunction "1_1") (pintype "passive"))
    )
    (net (code "20") (name "/RA") (class "Default")
      (node (ref "IC5") (pin "1") (pinfunction "R_1") (pintype "bidirectional"))
      (node (ref "R14") (pin "2") (pinfunction "2_2") (pintype "passive"))
      (node (ref "U2") (pin "1") (pinfunction "A_1") (pintype "bidirectional"))
    )
    (net (code "21") (name "/RB") (class "Default")
      (node (ref "IC6") (pin "1") (pinfunction "R_1") (pintype "bidirectional"))
      (node (ref "R15") (pin "2") (pinfunction "2_2") (pintype "passive"))
      (node (ref "U2") (pin "2") (pinfunction "B_2") (pintype "bidirectional"))
    )
    (net (code "22") (name "/RS232_RXI_INT") (class "Default")
      (node (ref "J1") (pin "6") (pintype "passive"))
      (node (ref "JP2") (pin "1") (pinfunction "1_1") (pintype "passive"))
    )
    (net (code "23") (name "/RS232_TXO_INT") (class "Default")
      (node (ref "J1") (pin "5") (pintype "passive"))
      (node (ref "JP1") (pin "1") (pinfunction "1_1") (pintype "passive"))
    )
    (net (code "24") (name "/RS422_A") (class "Default")
      (node (ref "IC6") (pin "6") (pinfunction "A_6") (pintype "bidirectional"))
      (node (ref "R21") (pin "1") (pinfunction "1_1") (pintype "passive"))
    )
    (net (code "25") (name "/RS422_B") (class "Default")
      (node (ref "IC6") (pin "7") (pinfunction "B_7") (pintype "bidirectional"))
      (node (ref "R19") (pin "1") (pinfunction "1_1") (pintype "passive"))
    )
    (net (code "26") (name "/RS422_RXI") (class "Default")
      (node (ref "D11") (pin "1") (pinfunction "1_1") (pintype "bidirectional"))
      (node (ref "JP2") (pin "2") (pinfunction "2_2") (pintype "passive"))
      (node (ref "R13") (pin "2") (pinfunction "2_2") (pintype "passive"))
      (node (ref "U2") (pin "4") (pinfunction "Y_4") (pintype "bidirectional"))
    )
    (net (code "27") (name "/RS422_S") (class "Default")
      (node (ref "C15") (pin "1") (pinfunction "1_1") (pintype "passive"))
      (node (ref "R17") (pin "1") (pinfunction "1_1") (pintype "passive"))
      (node (ref "R23") (pin "2") (pinfunction "2_2") (pintype "passive"))
    )
    (net (code "28") (name "/RS422_TXO") (class "Default")
      (node (ref "D10") (pin "1") (pinfunction "1_1") (pintype "bidirectional"))
      (node (ref "IC5") (pin "4") (pinfunction "D_4") (pintype "bidirectional"))
      (node (ref "JP1") (pin "2") (pinfunction "2_2") (pintype "passive"))
      (node (ref "R12") (pin "2") (pinfunction "2_2") (pintype "passive"))
    )
    (net (code "29") (name "/RS422_Y_RS485_A") (class "Default")
      (node (ref "IC5") (pin "6") (pinfunction "A_6") (pintype "bidirectional"))
      (node (ref "R20") (pin "1") (pinfunction "1_1") (pintype "passive"))
    )
    (net (code "30") (name "/RS422_Z_RS485_B") (class "Default")
      (node (ref "IC5") (pin "7") (pinfunction "B_7") (pintype "bidirectional"))
      (node (ref "R18") (pin "1") (pinfunction "1_1") (pintype "passive"))
    )
    (net (code "31") (name "/RS485_S") (class "Default")
      (node (ref "C14") (pin "1") (pinfunction "1_1") (pintype "passive"))
      (node (ref "R16") (pin "1") (pinfunction "1_1") (pintype "passive"))
      (node (ref "R22") (pin "2") (pinfunction "2_2") (pintype "passive"))
    )
    (net (code "32") (name "/SW") (class "Default")
      (node (ref "IC1") (pin "1") (pinfunction "SW_1") (pintype "bidirectional"))
      (node (ref "L2") (pin "2") (pinfunction "2_2") (pintype "passive"))
    )
    (net (code "33") (name "/SYNC") (class "Default")
      (node (ref "J2") (pin "8") (pinfunction "8_8") (pintype "bidirectional"))
      (node (ref "JP6") (pin "2") (pinfunction "2_2") (pintype "passive"))
    )
    (net (code "34") (name "/SYNC_IN") (class "Default")
      (node (ref "JP6") (pin "3") (pinfunction "3_3") (pintype "passive"))
      (node (ref "R10") (pin "2") (pinfunction "2_2") (pintype "passive"))
    )
    (net (code "35") (name "/SYNC_IN_INT") (class "Default")
      (node (ref "D7") (pin "1") (pinfunction "1_1") (pintype "bidirectional"))
      (node (ref "IC4") (pin "2") (pinfunction "A_2") (pintype "bidirectional"))
      (node (ref "R10") (pin "1") (pinfunction "1_1") (pintype "passive"))
      (node (ref "R6") (pin "2") (pinfunction "2_2") (pintype "passive"))
      (node (ref "Z3") (pin "1") (pinfunction "K_1") (pintype "bidirectional"))
    )
    (net (code "36") (name "/SYNC_OUT") (class "Default")
      (node (ref "JP6") (pin "1") (pinfunction "1_1") (pintype "passive"))
      (node (ref "R9") (pin "2") (pinfunction "2_2") (pintype "passive"))
    )
    (net (code "37") (name "/SYNC_OUT_INT") (class "Default")
      (node (ref "D9") (pin "1") (pinfunction "1_1") (pintype "bidirectional"))
      (node (ref "R9") (pin "1") (pinfunction "1_1") (pintype "passive"))
      (node (ref "U1") (pin "4") (pinfunction "Y_4") (pintype "bidirectional"))
    )
    (net (code "38") (name "/YA") (class "Default")
      (node (ref "C19") (pin "1") (pinfunction "1_1") (pintype "passive"))
      (node (ref "D12") (pin "2") (pinfunction "2_2") (pintype "bidirectional"))
      (node (ref "J2") (pin "4") (pinfunction "4_4") (pintype "bidirectional"))
      (node (ref "JP9") (pin "1") (pinfunction "1_1") (pintype "passive"))
      (node (ref "R20") (pin "2") (pinfunction "2_2") (pintype "passive"))
    )
    (net (code "39") (name "/YA_J") (class "Default")
      (node (ref "JP9") (pin "2") (pinfunction "2_2") (pintype "passive"))
      (node (ref "R22") (pin "1") (pinfunction "1_1") (pintype "passive"))
    )
    (net (code "40") (name "/YB_J") (class "Default")
      (node (ref "JP7") (pin "1") (pinfunction "1_1") (pintype "passive"))
      (node (ref "R16") (pin "2") (pinfunction "2_2") (pintype "passive"))
    )
    (net (code "41") (name "/ZB") (class "Default")
      (node (ref "C12") (pin "2") (pinfunction "2_2") (pintype "passive"))
      (node (ref "D12") (pin "1") (pinfunction "1_1") (pintype "bidirectional"))
      (node (ref "J2") (pin "3") (pinfunction "3_3") (pintype "bidirectional"))
      (node (ref "JP7") (pin "2") (pinfunction "2_2") (pintype "passive"))
      (node (ref "R18") (pin "2") (pinfunction "2_2") (pintype "passive"))
    )
    (net (code "42") (name "GND") (class "Default")
      (node (ref "C10") (pin "1") (pinfunction "1_1") (pintype "passive"))
      (node (ref "C11") (pin "1") (pinfunction "1_1") (pintype "passive"))
      (node (ref "C12") (pin "1") (pinfunction "1_1") (pintype "passive"))
      (node (ref "C13") (pin "1") (pinfunction "1_1") (pintype "passive"))
      (node (ref "C14") (pin "2") (pinfunction "2_2") (pintype "passive"))
      (node (ref "C15") (pin "2") (pinfunction "2_2") (pintype "passive"))
      (node (ref "C16") (pin "2") (pinfunction "2_2") (pintype "passive"))
      (node (ref "C17") (pin "2") (pinfunction "2_2") (pintype "passive"))
      (node (ref "C18") (pin "2") (pinfunction "2_2") (pintype "passive"))
      (node (ref "C19") (pin "2") (pinfunction "2_2") (pintype "passive"))
      (node (ref "C20") (pin "2") (pinfunction "2_2") (pintype "passive"))
      (node (ref "C3") (pin "1") (pinfunction "1_1") (pintype "passive"))
      (node (ref "C4") (pin "1") (pinfunction "1_1") (pintype "passive"))
      (node (ref "C5") (pin "2") (pinfunction "2_2") (pintype "passive"))
      (node (ref "C6") (pin "1") (pinfunction "1_1") (pintype "passive"))
      (node (ref "C7") (pin "1") (pinfunction "1_1") (pintype "passive"))
      (node (ref "C8") (pin "1") (pinfunction "1_1") (pintype "passive"))
      (node (ref "C9") (pin "1") (pinfunction "1_1") (pintype "passive"))
      (node (ref "D10") (pin "2") (pinfunction "2_2") (pintype "bidirectional"))
      (node (ref "D11") (pin "2") (pinfunction "2_2") (pintype "bidirectional"))
      (node (ref "D12") (pin "3") (pinfunction "3_3") (pintype "bidirectional"))
      (node (ref "D13") (pin "3") (pinfunction "3_3") (pintype "bidirectional"))
      (node (ref "D2") (pin "2") (pinfunction "2_2") (pintype "bidirectional"))
      (node (ref "D3") (pin "2") (pinfunction "A_2") (pintype "bidirectional"))
      (node (ref "D4") (pin "1") (pinfunction "1_1") (pintype "bidirectional"))
      (node (ref "D5") (pin "2") (pinfunction "2_2") (pintype "bidirectional"))
      (node (ref "D6") (pin "2") (pinfunction "2_2") (pintype "bidirectional"))
      (node (ref "D7") (pin "2") (pinfunction "2_2") (pintype "bidirectional"))
      (node (ref "D8") (pin "2") (pinfunction "2_2") (pintype "bidirectional"))
      (node (ref "D9") (pin "2") (pinfunction "2_2") (pintype "bidirectional"))
      (node (ref "IC1") (pin "2") (pinfunction "GND_2") (pintype "bidirectional"))
      (node (ref "IC2") (pin "2") (pinfunction "GND_2") (pintype "bidirectional"))
      (node (ref "IC3") (pin "2") (pinfunction "V-_2") (pintype "input"))
      (node (ref "IC4") (pin "3") (pinfunction "GND_3") (pintype "bidirectional"))
      (node (ref "IC5") (pin "5") (pinfunction "GND_5") (pintype "bidirectional"))
      (node (ref "IC6") (pin "5") (pinfunction "GND_5") (pintype "bidirectional"))
      (node (ref "J2") (pin "2") (pinfunction "2_2") (pintype "bidirectional"))
      (node (ref "J3") (pin "8") (pintype "passive"))
      (node (ref "J5") (pin "8") (pintype "passive"))
      (node (ref "R11") (pin "1") (pinfunction "1_1") (pintype "passive"))
      (node (ref "R2") (pin "2") (pinfunction "2_2") (pintype "passive"))
      (node (ref "R3") (pin "2") (pinfunction "2_2") (pintype "passive"))
      (node (ref "R8") (pin "2") (pinfunction "2_2") (pintype "passive"))
      (node (ref "U1") (pin "3") (pinfunction "GND_3") (pintype "bidirectional"))
      (node (ref "U2") (pin "3") (pinfunction "GND_3") (pintype "bidirectional"))
      (node (ref "Z2") (pin "1") (pintype "passive"))
      (node (ref "Z3") (pin "2") (pinfunction "A_2") (pintype "bidirectional"))
    )
    (net (code "43") (name "VCC") (class "Default")
      (node (ref "C10") (pin "2") (pinfunction "2_2") (pintype "passive"))
      (node (ref "C16") (pin "1") (pinfunction "1_1") (pintype "passive"))
      (node (ref "C17") (pin "1") (pinfunction "1_1") (pintype "passive"))
      (node (ref "C18") (pin "1") (pinfunction "1_1") (pintype "passive"))
      (node (ref "C3") (pin "2") (pinfunction "2_2") (pintype "passive"))
      (node (ref "D2") (pin "1") (pinfunction "1_1") (pintype "bidirectional"))
      (node (ref "IC4") (pin "5") (pinfunction "VCC_5") (pintype "bidirectional"))
      (node (ref "IC5") (pin "2") (pinfunction "~{RE}_2") (pintype "bidirectional"))
      (node (ref "IC5") (pin "3") (pinfunction "~{SHDN}_3") (pintype "bidirectional"))
      (node (ref "IC5") (pin "8") (pinfunction "VCC_8") (pintype "bidirectional"))
      (node (ref "IC6") (pin "2") (pinfunction "~{RE}_2") (pintype "bidirectional"))
      (node (ref "IC6") (pin "3") (pinfunction "~{SHDN}_3") (pintype "bidirectional"))
      (node (ref "IC6") (pin "4") (pinfunction "D_4") (pintype "bidirectional"))
      (node (ref "IC6") (pin "8") (pinfunction "VCC_8") (pintype "bidirectional"))
      (node (ref "J1") (pin "8") (pintype "passive"))
      (node (ref "J4") (pin "8") (pintype "passive"))
      (node (ref "L2") (pin "1") (pinfunction "1_1") (pintype "passive"))
      (node (ref "R12") (pin "1") (pinfunction "1_1") (pintype "passive"))
      (node (ref "R13") (pin "1") (pinfunction "1_1") (pintype "passive"))
      (node (ref "R14") (pin "1") (pinfunction "1_1") (pintype "passive"))
      (node (ref "R15") (pin "1") (pinfunction "1_1") (pintype "passive"))
      (node (ref "R7") (pin "1") (pinfunction "1_1") (pintype "passive"))
      (node (ref "U2") (pin "5") (pinfunction "VCC_5") (pintype "bidirectional"))
      (node (ref "Z2") (pin "2") (pintype "passive"))
    )
    (net (code "44") (name "VIN") (class "Default")
      (node (ref "D1") (pin "1") (pinfunction "K_1") (pintype "bidirectional"))
      (node (ref "J5") (pin "7") (pintype "passive"))
    )
    (net (code "45") (name "V_BATT") (class "Default")
      (node (ref "C11") (pin "2") (pinfunction "2_2") (pintype "passive"))
      (node (ref "C4") (pin "2") (pinfunction "2_2") (pintype "passive"))
      (node (ref "C9") (pin "2") (pinfunction "2_2") (pintype "passive"))
      (node (ref "IC1") (pin "4") (pinfunction "VOUT_4") (pintype "bidirectional"))
      (node (ref "IC3") (pin "5") (pinfunction "V+_5") (pintype "input"))
      (node (ref "R6") (pin "1") (pinfunction "1_1") (pintype "passive"))
      (node (ref "U1") (pin "5") (pinfunction "VCC_5") (pintype "bidirectional"))
    )
    (net (code "46") (name "unconnected-(IC1-NC_1-Pad3)") (class "Default")
      (node (ref "IC1") (pin "3") (pinfunction "NC_1_3") (pintype "bidirectional"))
    )
    (net (code "47") (name "unconnected-(IC1-NC_2-Pad5)") (class "Default")
      (node (ref "IC1") (pin "5") (pinfunction "NC_2_5") (pintype "bidirectional"))
    )
    (net (code "48") (name "unconnected-(IC4-N.C.-Pad1)") (class "Default")
      (node (ref "IC4") (pin "1") (pinfunction "N.C._1") (pintype "passive"))
    )
    (net (code "49") (name "unconnected-(J1-Pad1)") (class "Default")
      (node (ref "J1") (pin "1") (pintype "passive"))
    )
    (net (code "50") (name "unconnected-(J1-Pad2)") (class "Default")
      (node (ref "J1") (pin "2") (pintype "passive"))
    )
    (net (code "51") (name "unconnected-(J1-Pad3)") (class "Default")
      (node (ref "J1") (pin "3") (pintype "passive"))
    )
    (net (code "52") (name "unconnected-(J1-Pad4)") (class "Default")
      (node (ref "J1") (pin "4") (pintype "passive"))
    )
    (net (code "53") (name "unconnected-(J3-Pad1)") (class "Default")
      (node (ref "J3") (pin "1") (pintype "passive"))
    )
    (net (code "54") (name "unconnected-(J3-Pad2)") (class "Default")
      (node (ref "J3") (pin "2") (pintype "passive"))
    )
    (net (code "55") (name "unconnected-(J3-Pad3)") (class "Default")
      (node (ref "J3") (pin "3") (pintype "passive"))
    )
    (net (code "56") (name "unconnected-(J3-Pad4)") (class "Default")
      (node (ref "J3") (pin "4") (pintype "passive"))
    )
    (net (code "57") (name "unconnected-(J3-Pad5)") (class "Default")
      (node (ref "J3") (pin "5") (pintype "passive"))
    )
    (net (code "58") (name "unconnected-(J3-Pad6)") (class "Default")
      (node (ref "J3") (pin "6") (pintype "passive"))
    )
    (net (code "59") (name "unconnected-(J3-Pad7)") (class "Default")
      (node (ref "J3") (pin "7") (pintype "passive"))
    )
    (net (code "60") (name "unconnected-(J4-Pad1)") (class "Default")
      (node (ref "J4") (pin "1") (pintype "passive"))
    )
    (net (code "61") (name "unconnected-(J4-Pad2)") (class "Default")
      (node (ref "J4") (pin "2") (pintype "passive"))
    )
    (net (code "62") (name "unconnected-(J4-Pad3)") (class "Default")
      (node (ref "J4") (pin "3") (pintype "passive"))
    )
    (net (code "63") (name "unconnected-(J4-Pad4)") (class "Default")
      (node (ref "J4") (pin "4") (pintype "passive"))
    )
    (net (code "64") (name "unconnected-(J4-Pad5)") (class "Default")
      (node (ref "J4") (pin "5") (pintype "passive"))
    )
    (net (code "65") (name "unconnected-(J4-Pad6)") (class "Default")
      (node (ref "J4") (pin "6") (pintype "passive"))
    )
    (net (code "66") (name "unconnected-(J4-Pad7)") (class "Default")
      (node (ref "J4") (pin "7") (pintype "passive"))
    )
    (net (code "67") (name "unconnected-(J5-Pad1)") (class "Default")
      (node (ref "J5") (pin "1") (pintype "passive"))
    )
    (net (code "68") (name "unconnected-(J5-Pad2)") (class "Default")
      (node (ref "J5") (pin "2") (pintype "passive"))
    )
    (net (code "69") (name "unconnected-(J5-Pad4)") (class "Default")
      (node (ref "J5") (pin "4") (pintype "passive"))
    )
    (net (code "70") (name "unconnected-(J5-Pad5)") (class "Default")
      (node (ref "J5") (pin "5") (pintype "passive"))
    )
    (net (code "71") (name "unconnected-(J5-Pad6)") (class "Default")
      (node (ref "J5") (pin "6") (pintype "passive"))
    )
    (net (code "72") (name "unconnected-(U1-NC-Pad1)") (class "Default")
      (node (ref "U1") (pin "1") (pinfunction "NC_1") (pintype "passive"))
    )
  )
)
